# CODEC.net
KiCad netlist of a schematic drawn in Altium Designer
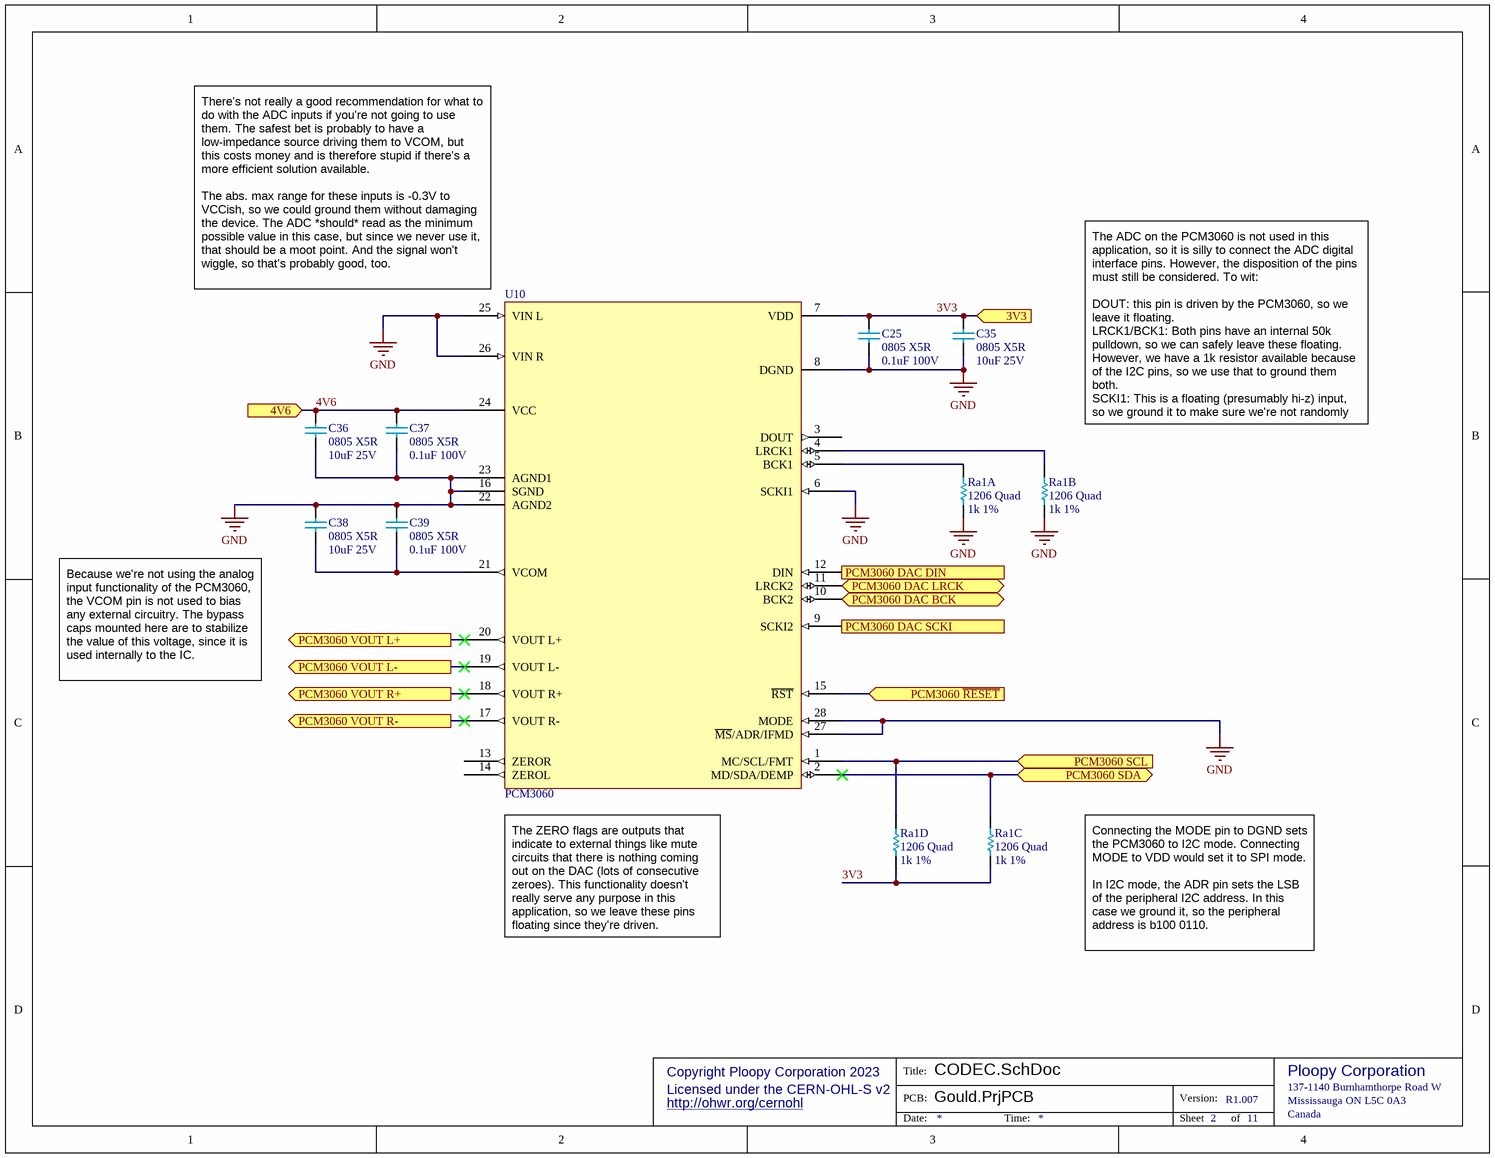
[diagram p0: CODEC.SchDoc]

(export (version "E")
  (design (tool "Eeschema 10.0.6"))
  (components
    (comp (ref "C25")
      (value "0805 X5R")
      (footprint "0805 - TALL")
      (description "0805, X5R or better")
      (fields (field (name "ALTIUM_VALUE") "0.1uF 100V"))
      (libsource (lib "Chip_Passives") (part "Cap 0.1uF 100V"))
    )
    (comp (ref "C35")
      (value "0805 X5R")
      (footprint "0805 - TALL")
      (description "0805, X5R or better")
      (fields (field (name "ALTIUM_VALUE") "10uF 25V"))
      (libsource (lib "Chip_Passives") (part "Cap 10uF 25V"))
    )
    (comp (ref "C36")
      (value "0805 X5R")
      (footprint "0805 - TALL")
      (description "0805, X5R or better")
      (fields (field (name "ALTIUM_VALUE") "10uF 25V"))
      (libsource (lib "Chip_Passives") (part "Cap 10uF 25V"))
    )
    (comp (ref "C37")
      (value "0805 X5R")
      (footprint "0805 - TALL")
      (description "0805, X5R or better")
      (fields (field (name "ALTIUM_VALUE") "0.1uF 100V"))
      (libsource (lib "Chip_Passives") (part "Cap 0.1uF 100V"))
    )
    (comp (ref "C38")
      (value "0805 X5R")
      (footprint "0805 - TALL")
      (description "0805, X5R or better")
      (fields (field (name "ALTIUM_VALUE") "10uF 25V"))
      (libsource (lib "Chip_Passives") (part "Cap 10uF 25V"))
    )
    (comp (ref "C39")
      (value "0805 X5R")
      (footprint "0805 - TALL")
      (description "0805, X5R or better")
      (fields (field (name "ALTIUM_VALUE") "0.1uF 100V"))
      (libsource (lib "Chip_Passives") (part "Cap 0.1uF 100V"))
    )
    (comp (ref "Ra1")
      (value "1206 Quad")
      (footprint "4x 1k 1% - CAC-80P320X160-8M")
      (description "Chip resistor")
      (fields (field (name "ALTIUM_VALUE") "1k 1%"))
      (libsource (lib "Chip_Passives") (part "Quad Res 1k 1% 1206"))
    )
    (comp (ref "U10")
      (value "PCM3060")
      (footprint "PCM3060 - TSOP65P640X120-28M")
      (description "24-BIT, 96/192-kHz ASYNCHRONOUS STEREO AUDIO CODEC")
      (libsource (lib "Analog") (part "PCM3060"))
    )
  )
  (nets
    (net (code "1") (name "/3V3") (class "Default")
      (node (ref "C25") (pin "2") (pinfunction "2_2") (pintype "passive"))
      (node (ref "C35") (pin "2") (pinfunction "2_2") (pintype "passive"))
      (node (ref "Ra1") (pin "5") (pinfunction "5_5") (pintype "passive"))
      (node (ref "Ra1") (pin "6") (pinfunction "6_6") (pintype "passive"))
      (node (ref "U10") (pin "7") (pinfunction "VDD_7") (pintype "passive"))
    )
    (net (code "2") (name "/4V6") (class "Default")
      (node (ref "C36") (pin "2") (pinfunction "2_2") (pintype "passive"))
      (node (ref "C37") (pin "2") (pinfunction "2_2") (pintype "passive"))
      (node (ref "U10") (pin "24") (pinfunction "VCC_24") (pintype "passive"))
    )
    (net (code "3") (name "/PCM3060 DAC BCK") (class "Default")
      (node (ref "U10") (pin "10") (pinfunction "BCK2_10") (pintype "bidirectional"))
    )
    (net (code "4") (name "/PCM3060 DAC DIN") (class "Default")
      (node (ref "U10") (pin "12") (pinfunction "DIN_12") (pintype "input"))
    )
    (net (code "5") (name "/PCM3060 DAC LRCK") (class "Default")
      (node (ref "U10") (pin "11") (pinfunction "LRCK2_11") (pintype "bidirectional"))
    )
    (net (code "6") (name "/PCM3060 DAC SCKI") (class "Default")
      (node (ref "U10") (pin "9") (pinfunction "SCKI2_9") (pintype "input"))
    )
    (net (code "7") (name "/PCM3060 SCL") (class "Default")
      (node (ref "Ra1") (pin "4") (pinfunction "4_4") (pintype "passive"))
      (node (ref "U10") (pin "1") (pinfunction "MC/SCL/FMT_1") (pintype "input"))
    )
    (net (code "8") (name "/PCM3060 SDA") (class "Default")
      (node (ref "Ra1") (pin "3") (pinfunction "3_3") (pintype "passive"))
      (node (ref "U10") (pin "2") (pinfunction "MD/SDA/DEMP_2") (pintype "bidirectional"))
    )
    (net (code "9") (name "/PCM3060 VOUT L+") (class "Default")
      (node (ref "U10") (pin "20") (pinfunction "VOUT_L+_20") (pintype "output+no_connect"))
    )
    (net (code "10") (name "/PCM3060 VOUT L-") (class "Default")
      (node (ref "U10") (pin "19") (pinfunction "VOUT_L-_19") (pintype "output+no_connect"))
    )
    (net (code "11") (name "/PCM3060 VOUT R+") (class "Default")
      (node (ref "U10") (pin "18") (pinfunction "VOUT_R+_18") (pintype "output+no_connect"))
    )
    (net (code "12") (name "/PCM3060 VOUT R-") (class "Default")
      (node (ref "U10") (pin "17") (pinfunction "VOUT_R-_17") (pintype "output+no_connect"))
    )
    (net (code "13") (name "/PCM3060 ~{RESET}") (class "Default")
      (node (ref "U10") (pin "15") (pinfunction "~{RST}_15") (pintype "input"))
    )
    (net (code "14") (name "GND") (class "Default")
      (node (ref "C25") (pin "1") (pinfunction "1_1") (pintype "passive"))
      (node (ref "C35") (pin "1") (pinfunction "1_1") (pintype "passive"))
      (node (ref "C36") (pin "1") (pinfunction "1_1") (pintype "passive"))
      (node (ref "C37") (pin "1") (pinfunction "1_1") (pintype "passive"))
      (node (ref "C38") (pin "2") (pinfunction "2_2") (pintype "passive"))
      (node (ref "C39") (pin "2") (pinfunction "2_2") (pintype "passive"))
      (node (ref "Ra1") (pin "7") (pinfunction "7_7") (pintype "passive"))
      (node (ref "Ra1") (pin "8") (pinfunction "8_8") (pintype "passive"))
      (node (ref "U10") (pin "16") (pinfunction "SGND_16") (pintype "passive"))
      (node (ref "U10") (pin "22") (pinfunction "AGND2_22") (pintype "passive"))
      (node (ref "U10") (pin "23") (pinfunction "AGND1_23") (pintype "passive"))
      (node (ref "U10") (pin "25") (pinfunction "VIN_L_25") (pintype "input"))
      (node (ref "U10") (pin "26") (pinfunction "VIN_R_26") (pintype "input"))
      (node (ref "U10") (pin "27") (pinfunction "~{MS}/ADR/IFMD_27") (pintype "input"))
      (node (ref "U10") (pin "28") (pinfunction "MODE_28") (pintype "input"))
      (node (ref "U10") (pin "6") (pinfunction "SCKI1_6") (pintype "input"))
      (node (ref "U10") (pin "8") (pinfunction "DGND_8") (pintype "passive"))
    )
    (net (code "15") (name "Net-(U10-BCK1)") (class "Default")
      (node (ref "Ra1") (pin "1") (pinfunction "1_1") (pintype "passive"))
      (node (ref "U10") (pin "5") (pinfunction "BCK1_5") (pintype "bidirectional"))
    )
    (net (code "16") (name "Net-(U10-LRCK1)") (class "Default")
      (node (ref "Ra1") (pin "2") (pinfunction "2_2") (pintype "passive"))
      (node (ref "U10") (pin "4") (pinfunction "LRCK1_4") (pintype "bidirectional"))
    )
    (net (code "17") (name "Net-(U10-VCOM)") (class "Default")
      (node (ref "C38") (pin "1") (pinfunction "1_1") (pintype "passive"))
      (node (ref "C39") (pin "1") (pinfunction "1_1") (pintype "passive"))
      (node (ref "U10") (pin "21") (pinfunction "VCOM_21") (pintype "output"))
    )
    (net (code "18") (name "unconnected-(U10-DOUT-Pad3)") (class "Default")
      (node (ref "U10") (pin "3") (pinfunction "DOUT_3") (pintype "output"))
    )
    (net (code "19") (name "unconnected-(U10-ZEROL-Pad14)") (class "Default")
      (node (ref "U10") (pin "14") (pinfunction "ZEROL_14") (pintype "output"))
    )
    (net (code "20") (name "unconnected-(U10-ZEROR-Pad13)") (class "Default")
      (node (ref "U10") (pin "13") (pinfunction "ZEROR_13") (pintype "output"))
    )
  )
)
